# Interface.net
KiCad netlist of a schematic drawn in Altium Designer
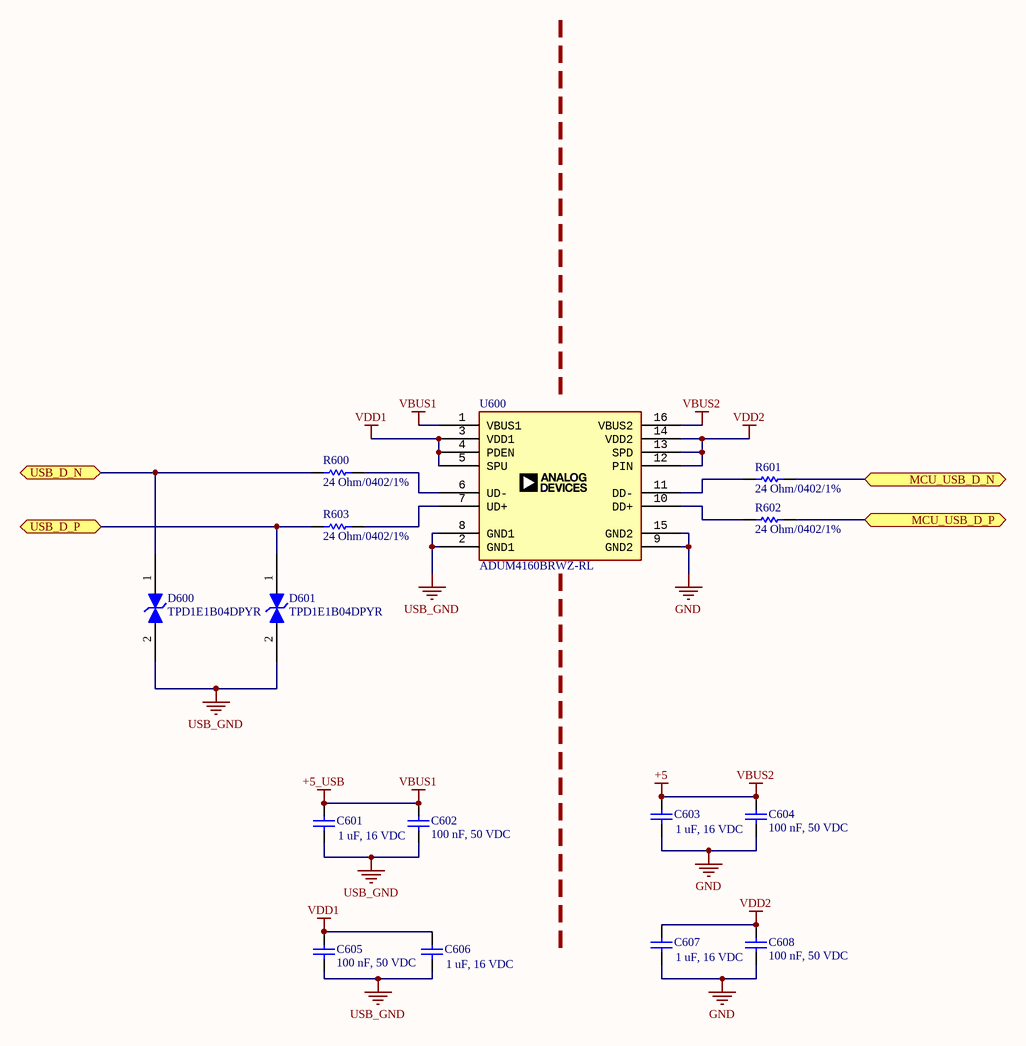
[diagram p0: Interface.SchDoc]

(export (version "E")
  (design (tool "Eeschema 10.0.6"))
  (components
    (comp (ref "C601")
      (value "1 uF, 16 VDC")
      (footprint "CAP_0603")
      (description "CAP, size 0603, 1 uF, 16 VDC")
      (fields (field (name "TOLERANCE") "+/-10%"))
      (libsource (lib "Altium_Ceramic_Cap") (part "0106031051016"))
    )
    (comp (ref "C602")
      (value "100 nF, 50 VDC")
      (footprint "CAP_0603")
      (description "CAP, size 0603, 100 nF, 50 VDC")
      (fields (field (name "TOLERANCE") "+/-10%"))
      (libsource (lib "Altium_Ceramic_Cap") (part "0106031041050"))
    )
    (comp (ref "C603")
      (value "1 uF, 16 VDC")
      (footprint "CAP_0603")
      (description "CAP, size 0603, 1 uF, 16 VDC")
      (fields (field (name "TOLERANCE") "+/-10%"))
      (libsource (lib "Altium_Ceramic_Cap") (part "0106031051016"))
    )
    (comp (ref "C604")
      (value "100 nF, 50 VDC")
      (footprint "CAP_0603")
      (description "CAP, size 0603, 100 nF, 50 VDC")
      (fields (field (name "TOLERANCE") "+/-10%"))
      (libsource (lib "Altium_Ceramic_Cap") (part "0106031041050"))
    )
    (comp (ref "C605")
      (value "100 nF, 50 VDC")
      (footprint "CAP_0603")
      (description "CAP, size 0603, 100 nF, 50 VDC")
      (fields (field (name "TOLERANCE") "+/-10%"))
      (libsource (lib "Altium_Ceramic_Cap") (part "0106031041050"))
    )
    (comp (ref "C606")
      (value "1 uF, 16 VDC")
      (footprint "CAP_0603")
      (description "CAP, size 0603, 1 uF, 16 VDC")
      (fields (field (name "TOLERANCE") "+/-10%"))
      (libsource (lib "Altium_Ceramic_Cap") (part "0106031051016"))
    )
    (comp (ref "C607")
      (value "1 uF, 16 VDC")
      (footprint "CAP_0603")
      (description "CAP, size 0603, 1 uF, 16 VDC")
      (fields (field (name "TOLERANCE") "+/-10%"))
      (libsource (lib "Altium_Ceramic_Cap") (part "0106031051016"))
    )
    (comp (ref "C608")
      (value "100 nF, 50 VDC")
      (footprint "CAP_0603")
      (description "CAP, size 0603, 100 nF, 50 VDC")
      (fields (field (name "TOLERANCE") "+/-10%"))
      (libsource (lib "Altium_Ceramic_Cap") (part "0106031041050"))
    )
    (comp (ref "D600")
      (value "TPD1E1B04DPYR")
      (footprint "DIO_TPD1E05U06DPYR")
      (description "8.5V (Typ) Clamp 6.3A (8/20µs) Ipp Tvs Diode Surface Mount 2-X1SON (1x.60)")
      (fields (field (name "MF") "Texas Instruments"))
      (libsource (lib "Giang_Diode") (part "TPD1E1B04DPYR"))
    )
    (comp (ref "D601")
      (value "TPD1E1B04DPYR")
      (footprint "DIO_TPD1E05U06DPYR")
      (description "8.5V (Typ) Clamp 6.3A (8/20µs) Ipp Tvs Diode Surface Mount 2-X1SON (1x.60)")
      (fields (field (name "MF") "Texas Instruments"))
      (libsource (lib "Giang_Diode") (part "TPD1E1B04DPYR"))
    )
    (comp (ref "R600")
      (value "24 Ohm/0402/1%")
      (footprint "R0402")
      (description "1/16W Thick Film Resistors 50V ±5% ±200ppm/℃ 24Ω 0402 Chip Resistor - Surface Mount ROHS")
      (fields (field (name "Comment") "Resistor 24 Ohm 0402 1%"))
      (libsource (lib "Giang_Resistor") (part "Resistor 24 Ohm 0402 1%"))
    )
    (comp (ref "R601")
      (value "24 Ohm/0402/1%")
      (footprint "R0402")
      (description "1/16W Thick Film Resistors 50V ±5% ±200ppm/℃ 24Ω 0402 Chip Resistor - Surface Mount ROHS")
      (fields (field (name "Comment") "Resistor 24 Ohm 0402 1%"))
      (libsource (lib "Giang_Resistor") (part "Resistor 24 Ohm 0402 1%"))
    )
    (comp (ref "R602")
      (value "24 Ohm/0402/1%")
      (footprint "R0402")
      (description "1/16W Thick Film Resistors 50V ±5% ±200ppm/℃ 24Ω 0402 Chip Resistor - Surface Mount ROHS")
      (fields (field (name "Comment") "Resistor 24 Ohm 0402 1%"))
      (libsource (lib "Giang_Resistor") (part "Resistor 24 Ohm 0402 1%"))
    )
    (comp (ref "R603")
      (value "24 Ohm/0402/1%")
      (footprint "R0402")
      (description "1/16W Thick Film Resistors 50V ±5% ±200ppm/℃ 24Ω 0402 Chip Resistor - Surface Mount ROHS")
      (fields (field (name "Comment") "Resistor 24 Ohm 0402 1%"))
      (libsource (lib "Giang_Resistor") (part "Resistor 24 Ohm 0402 1%"))
    )
    (comp (ref "U600")
      (value "ADUM4160BRWZ-RL")
      (footprint "SOIC16")
      (description "USB Digital Isolator 5000Vrms 1 Channel 12Mbps 25kV/µs CMTI 16-SOIC (0.295\", 7.50mm Width)")
      (libsource (lib "Giang_Isolators") (part "ADUM4160BRWZ-RL"))
    )
  )
  (nets
    (net (code "1") (name "+5") (class "Default")
      (node (ref "C603") (pin "2") (pinfunction "2_2") (pintype "passive"))
      (node (ref "C604") (pin "1") (pinfunction "1_1") (pintype "passive"))
      (node (ref "U600") (pin "16") (pinfunction "VBUS2_16") (pintype "passive"))
    )
    (net (code "2") (name "+5_USB") (class "Default")
      (node (ref "C601") (pin "2") (pinfunction "2_2") (pintype "passive"))
      (node (ref "C602") (pin "1") (pinfunction "1_1") (pintype "passive"))
      (node (ref "U600") (pin "1") (pinfunction "VBUS1_1") (pintype "passive"))
    )
    (net (code "3") (name "/MCU_USB_D_N") (class "Default")
      (node (ref "R601") (pin "2") (pinfunction "2_2") (pintype "passive"))
    )
    (net (code "4") (name "/MCU_USB_D_P") (class "Default")
      (node (ref "R602") (pin "2") (pinfunction "2_2") (pintype "passive"))
    )
    (net (code "5") (name "/USB_D_N") (class "Default")
      (node (ref "D600") (pin "1") (pinfunction "3_1") (pintype "passive"))
      (node (ref "R600") (pin "1") (pinfunction "1_1") (pintype "passive"))
    )
    (net (code "6") (name "/USB_D_P") (class "Default")
      (node (ref "D601") (pin "1") (pinfunction "3_1") (pintype "passive"))
      (node (ref "R603") (pin "1") (pinfunction "1_1") (pintype "passive"))
    )
    (net (code "7") (name "GND") (class "Default")
      (node (ref "C603") (pin "1") (pinfunction "1_1") (pintype "passive"))
      (node (ref "C604") (pin "2") (pinfunction "2_2") (pintype "passive"))
      (node (ref "C607") (pin "1") (pinfunction "1_1") (pintype "passive"))
      (node (ref "C608") (pin "2") (pinfunction "2_2") (pintype "passive"))
      (node (ref "U600") (pin "15") (pinfunction "GND2_15") (pintype "passive"))
      (node (ref "U600") (pin "9") (pinfunction "GND2_9") (pintype "passive"))
    )
    (net (code "8") (name "Net-(U600-DD+)") (class "Default")
      (node (ref "R602") (pin "1") (pinfunction "1_1") (pintype "passive"))
      (node (ref "U600") (pin "10") (pinfunction "DD+_10") (pintype "passive"))
    )
    (net (code "9") (name "Net-(U600-DD-)") (class "Default")
      (node (ref "R601") (pin "1") (pinfunction "1_1") (pintype "passive"))
      (node (ref "U600") (pin "11") (pinfunction "DD-_11") (pintype "passive"))
    )
    (net (code "10") (name "Net-(U600-UD+)") (class "Default")
      (node (ref "R603") (pin "2") (pinfunction "2_2") (pintype "passive"))
      (node (ref "U600") (pin "7") (pinfunction "UD+_7") (pintype "passive"))
    )
    (net (code "11") (name "Net-(U600-UD-)") (class "Default")
      (node (ref "R600") (pin "2") (pinfunction "2_2") (pintype "passive"))
      (node (ref "U600") (pin "6") (pinfunction "UD-_6") (pintype "passive"))
    )
    (net (code "12") (name "USB_GND") (class "Default")
      (node (ref "C601") (pin "1") (pinfunction "1_1") (pintype "passive"))
      (node (ref "C602") (pin "2") (pinfunction "2_2") (pintype "passive"))
      (node (ref "C605") (pin "2") (pinfunction "2_2") (pintype "passive"))
      (node (ref "C606") (pin "1") (pinfunction "1_1") (pintype "passive"))
      (node (ref "D600") (pin "2") (pinfunction "4_2") (pintype "passive"))
      (node (ref "D601") (pin "2") (pinfunction "4_2") (pintype "passive"))
      (node (ref "U600") (pin "2") (pinfunction "GND1_2") (pintype "passive"))
      (node (ref "U600") (pin "8") (pinfunction "GND1_8") (pintype "passive"))
    )
    (net (code "13") (name "VDD1") (class "Default")
      (node (ref "C605") (pin "1") (pinfunction "1_1") (pintype "passive"))
      (node (ref "C606") (pin "2") (pinfunction "2_2") (pintype "passive"))
      (node (ref "U600") (pin "3") (pinfunction "VDD1_3") (pintype "passive"))
      (node (ref "U600") (pin "4") (pinfunction "PDEN_4") (pintype "passive"))
      (node (ref "U600") (pin "5") (pinfunction "SPU_5") (pintype "passive"))
    )
    (net (code "14") (name "VDD2") (class "Default")
      (node (ref "C607") (pin "2") (pinfunction "2_2") (pintype "passive"))
      (node (ref "C608") (pin "1") (pinfunction "1_1") (pintype "passive"))
      (node (ref "U600") (pin "12") (pinfunction "PIN_12") (pintype "passive"))
      (node (ref "U600") (pin "13") (pinfunction "SPD_13") (pintype "passive"))
      (node (ref "U600") (pin "14") (pinfunction "VDD2_14") (pintype "passive"))
    )
  )
)
